# SCH13_RS232.net
KiCad netlist of a schematic drawn in Altium Designer
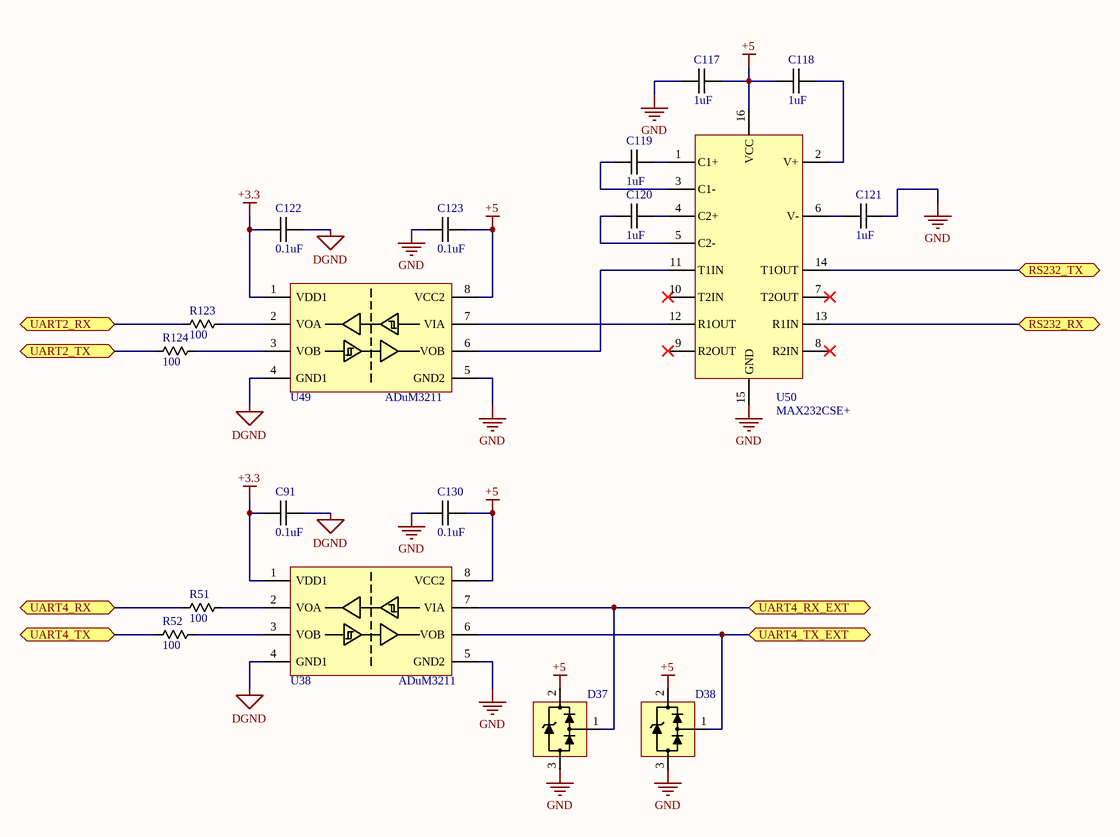
[diagram p0: SCH13_RS232.SchDoc]

(export (version "E")
  (design (tool "Eeschema 10.0.6"))
  (components
    (comp (ref "C91")
      (value "0.1uF")
      (footprint "chip_0603")
      (description "CAP, 0.1uF, ±10%, 16V, X7R, 0603")
      (fields (field (name "PART NUMBER") "CAP-00542") (field (name "TOLERANCE") "±10%"))
      (libsource (lib "Capacitors$") (part "CAP-00542"))
    )
    (comp (ref "C117")
      (value "1uF")
      (footprint "chip_0805")
      (description "CAP, 1uF, 10%, 16V, X7R, 0805")
      (fields (field (name "PART NUMBER") "CAP-00110") (field (name "TOLERANCE") "10%"))
      (libsource (lib "Capacitors$") (part "CAP-00110"))
    )
    (comp (ref "C118")
      (value "1uF")
      (footprint "chip_0805")
      (description "CAP, 1uF, 10%, 16V, X7R, 0805")
      (fields (field (name "PART NUMBER") "CAP-00110") (field (name "TOLERANCE") "10%"))
      (libsource (lib "Capacitors$") (part "CAP-00110"))
    )
    (comp (ref "C119")
      (value "1uF")
      (footprint "chip_0805")
      (description "CAP, 1uF, 10%, 16V, X7R, 0805")
      (fields (field (name "PART NUMBER") "CAP-00110") (field (name "TOLERANCE") "10%"))
      (libsource (lib "Capacitors$") (part "CAP-00110"))
    )
    (comp (ref "C120")
      (value "1uF")
      (footprint "chip_0805")
      (description "CAP, 1uF, 10%, 16V, X7R, 0805")
      (fields (field (name "PART NUMBER") "CAP-00110") (field (name "TOLERANCE") "10%"))
      (libsource (lib "Capacitors$") (part "CAP-00110"))
    )
    (comp (ref "C121")
      (value "1uF")
      (footprint "chip_0805")
      (description "CAP, 1uF, 10%, 16V, X7R, 0805")
      (fields (field (name "PART NUMBER") "CAP-00110") (field (name "TOLERANCE") "10%"))
      (libsource (lib "Capacitors$") (part "CAP-00110"))
    )
    (comp (ref "C122")
      (value "0.1uF")
      (footprint "chip_0603")
      (description "CAP, 0.1uF, ±10%, 16V, X7R, 0603")
      (fields (field (name "PART NUMBER") "CAP-00542") (field (name "TOLERANCE") "±10%"))
      (libsource (lib "Capacitors$") (part "CAP-00542"))
    )
    (comp (ref "C123")
      (value "0.1uF")
      (footprint "chip_0603")
      (description "CAP, 0.1uF, ±10%, 16V, X7R, 0603")
      (fields (field (name "PART NUMBER") "CAP-00542") (field (name "TOLERANCE") "±10%"))
      (libsource (lib "Capacitors$") (part "CAP-00542"))
    )
    (comp (ref "C130")
      (value "0.1uF")
      (footprint "chip_0603")
      (description "CAP, 0.1uF, ±10%, 16V, X7R, 0603")
      (fields (field (name "PART NUMBER") "CAP-00542") (field (name "TOLERANCE") "±10%"))
      (libsource (lib "Capacitors$") (part "CAP-00542"))
    )
    (comp (ref "D37")
      (value "DLPT05")
      (footprint "sot-23-3")
      (description "TVS, Steering (Rail-Rail), 9.8V Clamping, 17A Peak Pulse, SOT-23")
      (fields (field (name "PART NUMBER") "DIO-00057") (field (name "MANUFACTURER") "Diodes Incorporated"))
      (libsource (lib "Diodes$") (part "DIO-00057"))
    )
    (comp (ref "D38")
      (value "DLPT05")
      (footprint "sot-23-3")
      (description "TVS, Steering (Rail-Rail), 9.8V Clamping, 17A Peak Pulse, SOT-23")
      (fields (field (name "PART NUMBER") "DIO-00057") (field (name "MANUFACTURER") "Diodes Incorporated"))
      (libsource (lib "Diodes$") (part "DIO-00057"))
    )
    (comp (ref "R51")
      (value "100")
      (footprint "chip_0603")
      (description "RES SMD 100 OHM 1% 1/4W 0603")
      (fields (field (name "PART NUMBER") "RES-00178") (field (name "TOLERANCE") "1%"))
      (libsource (lib "Resistors$") (part "RES-00178"))
    )
    (comp (ref "R52")
      (value "100")
      (footprint "chip_0603")
      (description "RES SMD 100 OHM 1% 1/4W 0603")
      (fields (field (name "PART NUMBER") "RES-00178") (field (name "TOLERANCE") "1%"))
      (libsource (lib "Resistors$") (part "RES-00178"))
    )
    (comp (ref "R123")
      (value "100")
      (footprint "chip_0603")
      (description "RES SMD 100 OHM 1% 1/4W 0603")
      (fields (field (name "PART NUMBER") "RES-00178") (field (name "TOLERANCE") "1%"))
      (libsource (lib "Resistors$") (part "RES-00178"))
    )
    (comp (ref "R124")
      (value "100")
      (footprint "chip_0603")
      (description "RES SMD 100 OHM 1% 1/4W 0603")
      (fields (field (name "PART NUMBER") "RES-00178") (field (name "TOLERANCE") "1%"))
      (libsource (lib "Resistors$") (part "RES-00178"))
    )
    (comp (ref "U38")
      (value "ADuM3211")
      (footprint "SO-8")
      (description "Digital Isolator, Dual-Channel, ADuM3211")
      (fields (field (name "PART NUMBER") "IFACE-00015") (field (name "MANUFACTURER") "Analog Devices"))
      (libsource (lib "Interfaces$") (part "IFACE-00015"))
    )
    (comp (ref "U49")
      (value "ADuM3211")
      (footprint "SO-8")
      (description "Digital Isolator, Dual-Channel, ADuM3211")
      (fields (field (name "PART NUMBER") "IFACE-00015") (field (name "MANUFACTURER") "Analog Devices"))
      (libsource (lib "Interfaces$") (part "IFACE-00015"))
    )
    (comp (ref "U50")
      (value "MAX232CSE+")
      (footprint "SO-16")
      (description "IC, RS-232 Transceiver, Dual Channel, SOIC-16")
      (fields (field (name "PART NUMBER") "IFACE-00031") (field (name "MANUFACTURER") "Maxim Integrated"))
      (libsource (lib "Interfaces$") (part "IFACE-00031"))
    )
  )
  (nets
    (net (code "1") (name "+3.3") (class "Default")
      (node (ref "C122") (pin "2") (pinfunction "2_2") (pintype "passive"))
      (node (ref "C91") (pin "2") (pinfunction "2_2") (pintype "passive"))
      (node (ref "U38") (pin "1") (pinfunction "VDD1_1") (pintype "passive"))
      (node (ref "U49") (pin "1") (pinfunction "VDD1_1") (pintype "passive"))
    )
    (net (code "2") (name "+5") (class "Default")
      (node (ref "C117") (pin "2") (pinfunction "2_2") (pintype "passive"))
      (node (ref "C118") (pin "1") (pinfunction "1_1") (pintype "passive"))
      (node (ref "C123") (pin "1") (pinfunction "1_1") (pintype "passive"))
      (node (ref "C130") (pin "1") (pinfunction "1_1") (pintype "passive"))
      (node (ref "D37") (pin "2") (pinfunction "VCC_2") (pintype "passive"))
      (node (ref "D38") (pin "2") (pinfunction "VCC_2") (pintype "passive"))
      (node (ref "U38") (pin "8") (pinfunction "VCC2_8") (pintype "passive"))
      (node (ref "U49") (pin "8") (pinfunction "VCC2_8") (pintype "passive"))
      (node (ref "U50") (pin "16") (pinfunction "VCC_16") (pintype "passive"))
    )
    (net (code "3") (name "/RS232_RX") (class "Default")
      (node (ref "U50") (pin "13") (pinfunction "R1IN_13") (pintype "passive"))
    )
    (net (code "4") (name "/RS232_TX") (class "Default")
      (node (ref "U50") (pin "14") (pinfunction "T1OUT_14") (pintype "passive"))
    )
    (net (code "5") (name "/UART2_RX") (class "Default")
      (node (ref "R123") (pin "1") (pinfunction "1_1") (pintype "passive"))
    )
    (net (code "6") (name "/UART2_TX") (class "Default")
      (node (ref "R124") (pin "1") (pinfunction "1_1") (pintype "passive"))
    )
    (net (code "7") (name "/UART4_RX") (class "Default")
      (node (ref "R51") (pin "1") (pinfunction "1_1") (pintype "passive"))
    )
    (net (code "8") (name "/UART4_RX_EXT") (class "Default")
      (node (ref "D37") (pin "1") (pinfunction "LINE_1") (pintype "passive"))
      (node (ref "U38") (pin "7") (pinfunction "VIA_7") (pintype "passive"))
    )
    (net (code "9") (name "/UART4_TX") (class "Default")
      (node (ref "R52") (pin "1") (pinfunction "1_1") (pintype "passive"))
    )
    (net (code "10") (name "/UART4_TX_EXT") (class "Default")
      (node (ref "D38") (pin "1") (pinfunction "LINE_1") (pintype "passive"))
      (node (ref "U38") (pin "6") (pinfunction "VOB_6") (pintype "passive"))
    )
    (net (code "11") (name "DGND") (class "Default")
      (node (ref "C122") (pin "1") (pinfunction "1_1") (pintype "passive"))
      (node (ref "C91") (pin "1") (pinfunction "1_1") (pintype "passive"))
      (node (ref "U38") (pin "4") (pinfunction "GND1_4") (pintype "passive"))
      (node (ref "U49") (pin "4") (pinfunction "GND1_4") (pintype "passive"))
    )
    (net (code "12") (name "GND") (class "Default")
      (node (ref "C117") (pin "1") (pinfunction "1_1") (pintype "passive"))
      (node (ref "C121") (pin "2") (pinfunction "2_2") (pintype "passive"))
      (node (ref "C123") (pin "2") (pinfunction "2_2") (pintype "passive"))
      (node (ref "C130") (pin "2") (pinfunction "2_2") (pintype "passive"))
      (node (ref "D37") (pin "3") (pinfunction "GND_3") (pintype "passive"))
      (node (ref "D38") (pin "3") (pinfunction "GND_3") (pintype "passive"))
      (node (ref "U38") (pin "5") (pinfunction "GND2_5") (pintype "passive"))
      (node (ref "U49") (pin "5") (pinfunction "GND2_5") (pintype "passive"))
      (node (ref "U50") (pin "15") (pinfunction "GND_15") (pintype "passive"))
    )
    (net (code "13") (name "Net-(R52-Pad2)") (class "Default")
      (node (ref "R52") (pin "2") (pinfunction "2_2") (pintype "passive"))
      (node (ref "U38") (pin "3") (pinfunction "VOB_3") (pintype "passive"))
    )
    (net (code "14") (name "Net-(R124-Pad2)") (class "Default")
      (node (ref "R124") (pin "2") (pinfunction "2_2") (pintype "passive"))
      (node (ref "U49") (pin "3") (pinfunction "VOB_3") (pintype "passive"))
    )
    (net (code "15") (name "Net-(U38-VOA)") (class "Default")
      (node (ref "R51") (pin "2") (pinfunction "2_2") (pintype "passive"))
      (node (ref "U38") (pin "2") (pinfunction "VOA_2") (pintype "passive"))
    )
    (net (code "16") (name "Net-(U49-VIA)") (class "Default")
      (node (ref "U49") (pin "7") (pinfunction "VIA_7") (pintype "passive"))
      (node (ref "U50") (pin "12") (pinfunction "R1OUT_12") (pintype "passive"))
    )
    (net (code "17") (name "Net-(U49-VOA)") (class "Default")
      (node (ref "R123") (pin "2") (pinfunction "2_2") (pintype "passive"))
      (node (ref "U49") (pin "2") (pinfunction "VOA_2") (pintype "passive"))
    )
    (net (code "18") (name "Net-(U50-C1+)") (class "Default")
      (node (ref "C119") (pin "2") (pinfunction "2_2") (pintype "passive"))
      (node (ref "U50") (pin "1") (pinfunction "C1+_1") (pintype "passive"))
    )
    (net (code "19") (name "Net-(U50-C1-)") (class "Default")
      (node (ref "C119") (pin "1") (pinfunction "1_1") (pintype "passive"))
      (node (ref "U50") (pin "3") (pinfunction "C1-_3") (pintype "passive"))
    )
    (net (code "20") (name "Net-(U50-C2+)") (class "Default")
      (node (ref "C120") (pin "2") (pinfunction "2_2") (pintype "passive"))
      (node (ref "U50") (pin "4") (pinfunction "C2+_4") (pintype "passive"))
    )
    (net (code "21") (name "Net-(U50-C2-)") (class "Default")
      (node (ref "C120") (pin "1") (pinfunction "1_1") (pintype "passive"))
      (node (ref "U50") (pin "5") (pinfunction "C2-_5") (pintype "passive"))
    )
    (net (code "22") (name "Net-(U50-T1IN)") (class "Default")
      (node (ref "U49") (pin "6") (pinfunction "VOB_6") (pintype "passive"))
      (node (ref "U50") (pin "11") (pinfunction "T1IN_11") (pintype "passive"))
    )
    (net (code "23") (name "Net-(U50-V+)") (class "Default")
      (node (ref "C118") (pin "2") (pinfunction "2_2") (pintype "passive"))
      (node (ref "U50") (pin "2") (pinfunction "V+_2") (pintype "passive"))
    )
    (net (code "24") (name "Net-(U50-V-)") (class "Default")
      (node (ref "C121") (pin "1") (pinfunction "1_1") (pintype "passive"))
      (node (ref "U50") (pin "6") (pinfunction "V-_6") (pintype "passive"))
    )
    (net (code "25") (name "unconnected-(U50-R2IN-Pad8)") (class "Default")
      (node (ref "U50") (pin "8") (pinfunction "R2IN_8") (pintype "passive+no_connect"))
    )
    (net (code "26") (name "unconnected-(U50-R2OUT-Pad9)") (class "Default")
      (node (ref "U50") (pin "9") (pinfunction "R2OUT_9") (pintype "passive+no_connect"))
    )
    (net (code "27") (name "unconnected-(U50-T2IN-Pad10)") (class "Default")
      (node (ref "U50") (pin "10") (pinfunction "T2IN_10") (pintype "passive+no_connect"))
    )
    (net (code "28") (name "unconnected-(U50-T2OUT-Pad7)") (class "Default")
      (node (ref "U50") (pin "7") (pinfunction "T2OUT_7") (pintype "passive+no_connect"))
    )
  )
)
